# FMC_HPC_UFL_DEBUG_HPC_EF.net
KiCad netlist of a schematic drawn in Altium Designer
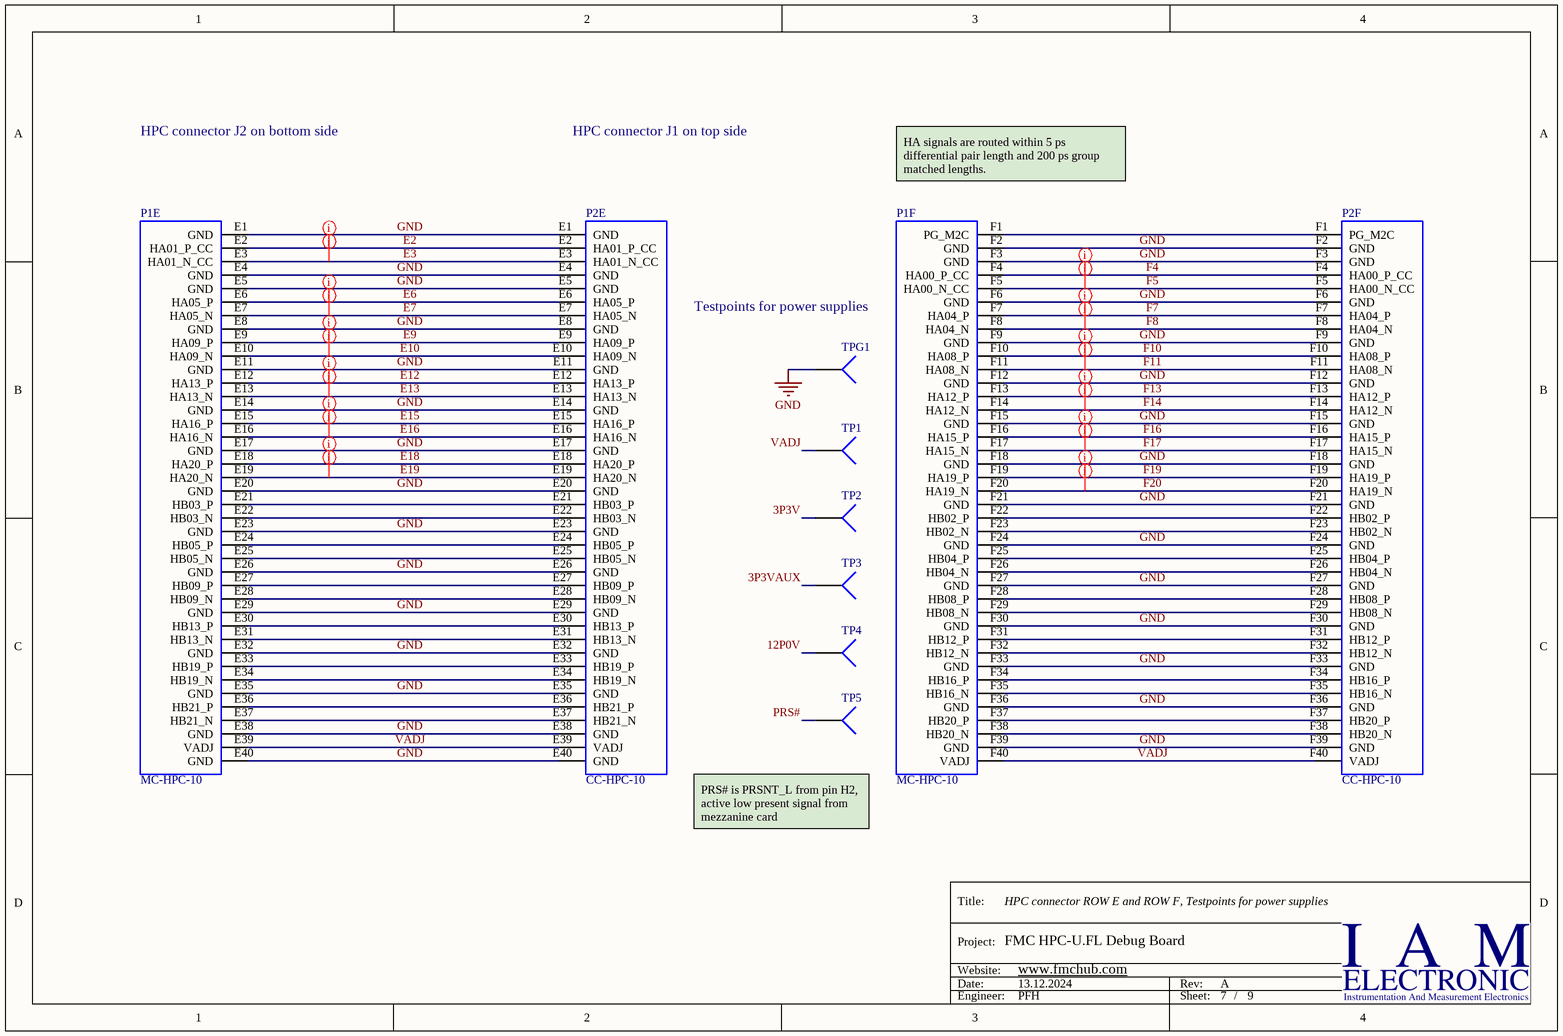
[diagram p0: FMC_HPC_UFL_DEBUG_HPC_EF.SchDoc]

(export (version "E")
  (design (tool "Eeschema 10.0.6"))
  (components
    (comp (ref "P1")
      (value "MC-HPC-10")
      (footprint "ASP-134488-01")
      (description "MC-HPC-10, FMC High-pin count connector, lead free, 400 I/Os, male, 10 mm mated stack height")
      (fields (field (name "MANUFACTURER") "Samtec") (field (name "PART") "ASP-134488-01"))
      (libsource (lib "VITA_57_FMC") (part "MC-HPC-10"))
    )
    (comp (ref "P2")
      (value "CC-HPC-10")
      (footprint "ASP-134486-01")
      (description "CC-HPC-10, FMC High-pin count connector, lead free, 400 I/Os, female, 10 mm mated stack height")
      (fields (field (name "MANUFACTURER") "Samtec") (field (name "PART") "ASP-134486-01"))
      (libsource (lib "VITA_57_FMC") (part "CC-HPC-10"))
    )
    (comp (ref "TP1")
      (value "~")
      (footprint "PIN1")
      (description "Socket")
      (fields (field (name "PUBLISHER") "Altium Limited"))
      (libsource (lib "Miscellaneous Connectors") (part "Socket"))
    )
    (comp (ref "TP2")
      (value "~")
      (footprint "PIN1")
      (description "Socket")
      (fields (field (name "PUBLISHER") "Altium Limited"))
      (libsource (lib "Miscellaneous Connectors") (part "Socket"))
    )
    (comp (ref "TP3")
      (value "~")
      (footprint "PIN1")
      (description "Socket")
      (fields (field (name "PUBLISHER") "Altium Limited"))
      (libsource (lib "Miscellaneous Connectors") (part "Socket"))
    )
    (comp (ref "TP4")
      (value "~")
      (footprint "PIN1")
      (description "Socket")
      (fields (field (name "PUBLISHER") "Altium Limited"))
      (libsource (lib "Miscellaneous Connectors") (part "Socket"))
    )
    (comp (ref "TP5")
      (value "~")
      (footprint "PIN1")
      (description "Socket")
      (fields (field (name "PUBLISHER") "Altium Limited"))
      (libsource (lib "Miscellaneous Connectors") (part "Socket"))
    )
    (comp (ref "TPG1")
      (value "~")
      (footprint "PIN1")
      (description "Socket")
      (fields (field (name "PUBLISHER") "Altium Limited"))
      (libsource (lib "Miscellaneous Connectors") (part "Socket"))
    )
  )
  (nets
    (net (code "1") (name "/3P3V") (class "Default")
      (node (ref "TP2") (pin "1") (pinfunction "1_1") (pintype "passive"))
    )
    (net (code "2") (name "/3P3VAUX") (class "Default")
      (node (ref "TP3") (pin "1") (pinfunction "1_1") (pintype "passive"))
    )
    (net (code "3") (name "/12P0V") (class "Default")
      (node (ref "TP4") (pin "1") (pinfunction "1_1") (pintype "passive"))
    )
    (net (code "4") (name "/E2") (class "Default")
      (node (ref "P1") (pin "E2") (pinfunction "HA01_P_CC_E2") (pintype "passive"))
      (node (ref "P2") (pin "E2") (pinfunction "HA01_P_CC_E2") (pintype "passive"))
    )
    (net (code "5") (name "/E3") (class "Default")
      (node (ref "P1") (pin "E3") (pinfunction "HA01_N_CC_E3") (pintype "passive"))
      (node (ref "P2") (pin "E3") (pinfunction "HA01_N_CC_E3") (pintype "passive"))
    )
    (net (code "6") (name "/E6") (class "Default")
      (node (ref "P1") (pin "E6") (pinfunction "HA05_P_E6") (pintype "passive"))
      (node (ref "P2") (pin "E6") (pinfunction "HA05_P_E6") (pintype "passive"))
    )
    (net (code "7") (name "/E7") (class "Default")
      (node (ref "P1") (pin "E7") (pinfunction "HA05_N_E7") (pintype "passive"))
      (node (ref "P2") (pin "E7") (pinfunction "HA05_N_E7") (pintype "passive"))
    )
    (net (code "8") (name "/E9") (class "Default")
      (node (ref "P1") (pin "E9") (pinfunction "HA09_P_E9") (pintype "passive"))
      (node (ref "P2") (pin "E9") (pinfunction "HA09_P_E9") (pintype "passive"))
    )
    (net (code "9") (name "/E10") (class "Default")
      (node (ref "P1") (pin "E10") (pinfunction "HA09_N_E10") (pintype "passive"))
      (node (ref "P2") (pin "E10") (pinfunction "HA09_N_E10") (pintype "passive"))
    )
    (net (code "10") (name "/E12") (class "Default")
      (node (ref "P1") (pin "E12") (pinfunction "HA13_P_E12") (pintype "passive"))
      (node (ref "P2") (pin "E12") (pinfunction "HA13_P_E12") (pintype "passive"))
    )
    (net (code "11") (name "/E13") (class "Default")
      (node (ref "P1") (pin "E13") (pinfunction "HA13_N_E13") (pintype "passive"))
      (node (ref "P2") (pin "E13") (pinfunction "HA13_N_E13") (pintype "passive"))
    )
    (net (code "12") (name "/E15") (class "Default")
      (node (ref "P1") (pin "E15") (pinfunction "HA16_P_E15") (pintype "passive"))
      (node (ref "P2") (pin "E15") (pinfunction "HA16_P_E15") (pintype "passive"))
    )
    (net (code "13") (name "/E16") (class "Default")
      (node (ref "P1") (pin "E16") (pinfunction "HA16_N_E16") (pintype "passive"))
      (node (ref "P2") (pin "E16") (pinfunction "HA16_N_E16") (pintype "passive"))
    )
    (net (code "14") (name "/E18") (class "Default")
      (node (ref "P1") (pin "E18") (pinfunction "HA20_P_E18") (pintype "passive"))
      (node (ref "P2") (pin "E18") (pinfunction "HA20_P_E18") (pintype "passive"))
    )
    (net (code "15") (name "/E19") (class "Default")
      (node (ref "P1") (pin "E19") (pinfunction "HA20_N_E19") (pintype "passive"))
      (node (ref "P2") (pin "E19") (pinfunction "HA20_N_E19") (pintype "passive"))
    )
    (net (code "16") (name "/F4") (class "Default")
      (node (ref "P1") (pin "F4") (pinfunction "HA00_P_CC_F4") (pintype "passive"))
      (node (ref "P2") (pin "F4") (pinfunction "HA00_P_CC_F4") (pintype "passive"))
    )
    (net (code "17") (name "/F5") (class "Default")
      (node (ref "P1") (pin "F5") (pinfunction "HA00_N_CC_F5") (pintype "passive"))
      (node (ref "P2") (pin "F5") (pinfunction "HA00_N_CC_F5") (pintype "passive"))
    )
    (net (code "18") (name "/F7") (class "Default")
      (node (ref "P1") (pin "F7") (pinfunction "HA04_P_F7") (pintype "passive"))
      (node (ref "P2") (pin "F7") (pinfunction "HA04_P_F7") (pintype "passive"))
    )
    (net (code "19") (name "/F8") (class "Default")
      (node (ref "P1") (pin "F8") (pinfunction "HA04_N_F8") (pintype "passive"))
      (node (ref "P2") (pin "F8") (pinfunction "HA04_N_F8") (pintype "passive"))
    )
    (net (code "20") (name "/F10") (class "Default")
      (node (ref "P1") (pin "F10") (pinfunction "HA08_P_F10") (pintype "passive"))
      (node (ref "P2") (pin "F10") (pinfunction "HA08_P_F10") (pintype "passive"))
    )
    (net (code "21") (name "/F11") (class "Default")
      (node (ref "P1") (pin "F11") (pinfunction "HA08_N_F11") (pintype "passive"))
      (node (ref "P2") (pin "F11") (pinfunction "HA08_N_F11") (pintype "passive"))
    )
    (net (code "22") (name "/F13") (class "Default")
      (node (ref "P1") (pin "F13") (pinfunction "HA12_P_F13") (pintype "passive"))
      (node (ref "P2") (pin "F13") (pinfunction "HA12_P_F13") (pintype "passive"))
    )
    (net (code "23") (name "/F14") (class "Default")
      (node (ref "P1") (pin "F14") (pinfunction "HA12_N_F14") (pintype "passive"))
      (node (ref "P2") (pin "F14") (pinfunction "HA12_N_F14") (pintype "passive"))
    )
    (net (code "24") (name "/F16") (class "Default")
      (node (ref "P1") (pin "F16") (pinfunction "HA15_P_F16") (pintype "passive"))
      (node (ref "P2") (pin "F16") (pinfunction "HA15_P_F16") (pintype "passive"))
    )
    (net (code "25") (name "/F17") (class "Default")
      (node (ref "P1") (pin "F17") (pinfunction "HA15_N_F17") (pintype "passive"))
      (node (ref "P2") (pin "F17") (pinfunction "HA15_N_F17") (pintype "passive"))
    )
    (net (code "26") (name "/F19") (class "Default")
      (node (ref "P1") (pin "F19") (pinfunction "HA19_P_F19") (pintype "passive"))
      (node (ref "P2") (pin "F19") (pinfunction "HA19_P_F19") (pintype "passive"))
    )
    (net (code "27") (name "/F20") (class "Default")
      (node (ref "P1") (pin "F20") (pinfunction "HA19_N_F20") (pintype "passive"))
      (node (ref "P2") (pin "F20") (pinfunction "HA19_N_F20") (pintype "passive"))
    )
    (net (code "28") (name "/PRS#") (class "Default")
      (node (ref "TP5") (pin "1") (pinfunction "1_1") (pintype "passive"))
    )
    (net (code "29") (name "/VADJ") (class "Default")
      (node (ref "P1") (pin "E39") (pinfunction "VADJ_E39") (pintype "passive"))
      (node (ref "P1") (pin "F40") (pinfunction "VADJ_F40") (pintype "passive"))
      (node (ref "P2") (pin "E39") (pinfunction "VADJ_E39") (pintype "passive"))
      (node (ref "P2") (pin "F40") (pinfunction "VADJ_F40") (pintype "passive"))
      (node (ref "TP1") (pin "1") (pinfunction "1_1") (pintype "passive"))
    )
    (net (code "30") (name "GND") (class "Default")
      (node (ref "P1") (pin "E1") (pinfunction "GND_E1") (pintype "passive"))
      (node (ref "P1") (pin "E11") (pinfunction "GND_E11") (pintype "passive"))
      (node (ref "P1") (pin "E14") (pinfunction "GND_E14") (pintype "passive"))
      (node (ref "P1") (pin "E17") (pinfunction "GND_E17") (pintype "passive"))
      (node (ref "P1") (pin "E20") (pinfunction "GND_E20") (pintype "passive"))
      (node (ref "P1") (pin "E23") (pinfunction "GND_E23") (pintype "passive"))
      (node (ref "P1") (pin "E26") (pinfunction "GND_E26") (pintype "passive"))
      (node (ref "P1") (pin "E29") (pinfunction "GND_E29") (pintype "passive"))
      (node (ref "P1") (pin "E32") (pinfunction "GND_E32") (pintype "passive"))
      (node (ref "P1") (pin "E35") (pinfunction "GND_E35") (pintype "passive"))
      (node (ref "P1") (pin "E38") (pinfunction "GND_E38") (pintype "passive"))
      (node (ref "P1") (pin "E4") (pinfunction "GND_E4") (pintype "passive"))
      (node (ref "P1") (pin "E40") (pinfunction "GND_E40") (pintype "passive"))
      (node (ref "P1") (pin "E5") (pinfunction "GND_E5") (pintype "passive"))
      (node (ref "P1") (pin "E8") (pinfunction "GND_E8") (pintype "passive"))
      (node (ref "P1") (pin "F12") (pinfunction "GND_F12") (pintype "passive"))
      (node (ref "P1") (pin "F15") (pinfunction "GND_F15") (pintype "passive"))
      (node (ref "P1") (pin "F18") (pinfunction "GND_F18") (pintype "passive"))
      (node (ref "P1") (pin "F2") (pinfunction "GND_F2") (pintype "passive"))
      (node (ref "P1") (pin "F21") (pinfunction "GND_F21") (pintype "passive"))
      (node (ref "P1") (pin "F24") (pinfunction "GND_F24") (pintype "passive"))
      (node (ref "P1") (pin "F27") (pinfunction "GND_F27") (pintype "passive"))
      (node (ref "P1") (pin "F3") (pinfunction "GND_F3") (pintype "passive"))
      (node (ref "P1") (pin "F30") (pinfunction "GND_F30") (pintype "passive"))
      (node (ref "P1") (pin "F33") (pinfunction "GND_F33") (pintype "passive"))
      (node (ref "P1") (pin "F36") (pinfunction "GND_F36") (pintype "passive"))
      (node (ref "P1") (pin "F39") (pinfunction "GND_F39") (pintype "passive"))
      (node (ref "P1") (pin "F6") (pinfunction "GND_F6") (pintype "passive"))
      (node (ref "P1") (pin "F9") (pinfunction "GND_F9") (pintype "passive"))
      (node (ref "P2") (pin "E1") (pinfunction "GND_E1") (pintype "passive"))
      (node (ref "P2") (pin "E11") (pinfunction "GND_E11") (pintype "passive"))
      (node (ref "P2") (pin "E14") (pinfunction "GND_E14") (pintype "passive"))
      (node (ref "P2") (pin "E17") (pinfunction "GND_E17") (pintype "passive"))
      (node (ref "P2") (pin "E20") (pinfunction "GND_E20") (pintype "passive"))
      (node (ref "P2") (pin "E23") (pinfunction "GND_E23") (pintype "passive"))
      (node (ref "P2") (pin "E26") (pinfunction "GND_E26") (pintype "passive"))
      (node (ref "P2") (pin "E29") (pinfunction "GND_E29") (pintype "passive"))
      (node (ref "P2") (pin "E32") (pinfunction "GND_E32") (pintype "passive"))
      (node (ref "P2") (pin "E35") (pinfunction "GND_E35") (pintype "passive"))
      (node (ref "P2") (pin "E38") (pinfunction "GND_E38") (pintype "passive"))
      (node (ref "P2") (pin "E4") (pinfunction "GND_E4") (pintype "passive"))
      (node (ref "P2") (pin "E40") (pinfunction "GND_E40") (pintype "passive"))
      (node (ref "P2") (pin "E5") (pinfunction "GND_E5") (pintype "passive"))
      (node (ref "P2") (pin "E8") (pinfunction "GND_E8") (pintype "passive"))
      (node (ref "P2") (pin "F12") (pinfunction "GND_F12") (pintype "passive"))
      (node (ref "P2") (pin "F15") (pinfunction "GND_F15") (pintype "passive"))
      (node (ref "P2") (pin "F18") (pinfunction "GND_F18") (pintype "passive"))
      (node (ref "P2") (pin "F2") (pinfunction "GND_F2") (pintype "passive"))
      (node (ref "P2") (pin "F21") (pinfunction "GND_F21") (pintype "passive"))
      (node (ref "P2") (pin "F24") (pinfunction "GND_F24") (pintype "passive"))
      (node (ref "P2") (pin "F27") (pinfunction "GND_F27") (pintype "passive"))
      (node (ref "P2") (pin "F3") (pinfunction "GND_F3") (pintype "passive"))
      (node (ref "P2") (pin "F30") (pinfunction "GND_F30") (pintype "passive"))
      (node (ref "P2") (pin "F33") (pinfunction "GND_F33") (pintype "passive"))
      (node (ref "P2") (pin "F36") (pinfunction "GND_F36") (pintype "passive"))
      (node (ref "P2") (pin "F39") (pinfunction "GND_F39") (pintype "passive"))
      (node (ref "P2") (pin "F6") (pinfunction "GND_F6") (pintype "passive"))
      (node (ref "P2") (pin "F9") (pinfunction "GND_F9") (pintype "passive"))
      (node (ref "TPG1") (pin "1") (pinfunction "1_1") (pintype "passive"))
    )
    (net (code "31") (name "Net-(P1E-HB03_N)") (class "Default")
      (node (ref "P1") (pin "E22") (pinfunction "HB03_N_E22") (pintype "passive"))
      (node (ref "P2") (pin "E22") (pinfunction "HB03_N_E22") (pintype "passive"))
    )
    (net (code "32") (name "Net-(P1E-HB03_P)") (class "Default")
      (node (ref "P1") (pin "E21") (pinfunction "HB03_P_E21") (pintype "passive"))
      (node (ref "P2") (pin "E21") (pinfunction "HB03_P_E21") (pintype "passive"))
    )
    (net (code "33") (name "Net-(P1E-HB05_N)") (class "Default")
      (node (ref "P1") (pin "E25") (pinfunction "HB05_N_E25") (pintype "passive"))
      (node (ref "P2") (pin "E25") (pinfunction "HB05_N_E25") (pintype "passive"))
    )
    (net (code "34") (name "Net-(P1E-HB05_P)") (class "Default")
      (node (ref "P1") (pin "E24") (pinfunction "HB05_P_E24") (pintype "passive"))
      (node (ref "P2") (pin "E24") (pinfunction "HB05_P_E24") (pintype "passive"))
    )
    (net (code "35") (name "Net-(P1E-HB09_N)") (class "Default")
      (node (ref "P1") (pin "E28") (pinfunction "HB09_N_E28") (pintype "passive"))
      (node (ref "P2") (pin "E28") (pinfunction "HB09_N_E28") (pintype "passive"))
    )
    (net (code "36") (name "Net-(P1E-HB09_P)") (class "Default")
      (node (ref "P1") (pin "E27") (pinfunction "HB09_P_E27") (pintype "passive"))
      (node (ref "P2") (pin "E27") (pinfunction "HB09_P_E27") (pintype "passive"))
    )
    (net (code "37") (name "Net-(P1E-HB13_N)") (class "Default")
      (node (ref "P1") (pin "E31") (pinfunction "HB13_N_E31") (pintype "passive"))
      (node (ref "P2") (pin "E31") (pinfunction "HB13_N_E31") (pintype "passive"))
    )
    (net (code "38") (name "Net-(P1E-HB13_P)") (class "Default")
      (node (ref "P1") (pin "E30") (pinfunction "HB13_P_E30") (pintype "passive"))
      (node (ref "P2") (pin "E30") (pinfunction "HB13_P_E30") (pintype "passive"))
    )
    (net (code "39") (name "Net-(P1E-HB19_N)") (class "Default")
      (node (ref "P1") (pin "E34") (pinfunction "HB19_N_E34") (pintype "passive"))
      (node (ref "P2") (pin "E34") (pinfunction "HB19_N_E34") (pintype "passive"))
    )
    (net (code "40") (name "Net-(P1E-HB19_P)") (class "Default")
      (node (ref "P1") (pin "E33") (pinfunction "HB19_P_E33") (pintype "passive"))
      (node (ref "P2") (pin "E33") (pinfunction "HB19_P_E33") (pintype "passive"))
    )
    (net (code "41") (name "Net-(P1E-HB21_N)") (class "Default")
      (node (ref "P1") (pin "E37") (pinfunction "HB21_N_E37") (pintype "passive"))
      (node (ref "P2") (pin "E37") (pinfunction "HB21_N_E37") (pintype "passive"))
    )
    (net (code "42") (name "Net-(P1E-HB21_P)") (class "Default")
      (node (ref "P1") (pin "E36") (pinfunction "HB21_P_E36") (pintype "passive"))
      (node (ref "P2") (pin "E36") (pinfunction "HB21_P_E36") (pintype "passive"))
    )
    (net (code "43") (name "Net-(P1F-HB02_N)") (class "Default")
      (node (ref "P1") (pin "F23") (pinfunction "HB02_N_F23") (pintype "passive"))
      (node (ref "P2") (pin "F23") (pinfunction "HB02_N_F23") (pintype "passive"))
    )
    (net (code "44") (name "Net-(P1F-HB02_P)") (class "Default")
      (node (ref "P1") (pin "F22") (pinfunction "HB02_P_F22") (pintype "passive"))
      (node (ref "P2") (pin "F22") (pinfunction "HB02_P_F22") (pintype "passive"))
    )
    (net (code "45") (name "Net-(P1F-HB04_N)") (class "Default")
      (node (ref "P1") (pin "F26") (pinfunction "HB04_N_F26") (pintype "passive"))
      (node (ref "P2") (pin "F26") (pinfunction "HB04_N_F26") (pintype "passive"))
    )
    (net (code "46") (name "Net-(P1F-HB04_P)") (class "Default")
      (node (ref "P1") (pin "F25") (pinfunction "HB04_P_F25") (pintype "passive"))
      (node (ref "P2") (pin "F25") (pinfunction "HB04_P_F25") (pintype "passive"))
    )
    (net (code "47") (name "Net-(P1F-HB08_N)") (class "Default")
      (node (ref "P1") (pin "F29") (pinfunction "HB08_N_F29") (pintype "passive"))
      (node (ref "P2") (pin "F29") (pinfunction "HB08_N_F29") (pintype "passive"))
    )
    (net (code "48") (name "Net-(P1F-HB08_P)") (class "Default")
      (node (ref "P1") (pin "F28") (pinfunction "HB08_P_F28") (pintype "passive"))
      (node (ref "P2") (pin "F28") (pinfunction "HB08_P_F28") (pintype "passive"))
    )
    (net (code "49") (name "Net-(P1F-HB12_N)") (class "Default")
      (node (ref "P1") (pin "F32") (pinfunction "HB12_N_F32") (pintype "passive"))
      (node (ref "P2") (pin "F32") (pinfunction "HB12_N_F32") (pintype "passive"))
    )
    (net (code "50") (name "Net-(P1F-HB12_P)") (class "Default")
      (node (ref "P1") (pin "F31") (pinfunction "HB12_P_F31") (pintype "passive"))
      (node (ref "P2") (pin "F31") (pinfunction "HB12_P_F31") (pintype "passive"))
    )
    (net (code "51") (name "Net-(P1F-HB16_N)") (class "Default")
      (node (ref "P1") (pin "F35") (pinfunction "HB16_N_F35") (pintype "passive"))
      (node (ref "P2") (pin "F35") (pinfunction "HB16_N_F35") (pintype "passive"))
    )
    (net (code "52") (name "Net-(P1F-HB16_P)") (class "Default")
      (node (ref "P1") (pin "F34") (pinfunction "HB16_P_F34") (pintype "passive"))
      (node (ref "P2") (pin "F34") (pinfunction "HB16_P_F34") (pintype "passive"))
    )
    (net (code "53") (name "Net-(P1F-HB20_N)") (class "Default")
      (node (ref "P1") (pin "F38") (pinfunction "HB20_N_F38") (pintype "passive"))
      (node (ref "P2") (pin "F38") (pinfunction "HB20_N_F38") (pintype "passive"))
    )
    (net (code "54") (name "Net-(P1F-HB20_P)") (class "Default")
      (node (ref "P1") (pin "F37") (pinfunction "HB20_P_F37") (pintype "passive"))
      (node (ref "P2") (pin "F37") (pinfunction "HB20_P_F37") (pintype "passive"))
    )
    (net (code "55") (name "Net-(P1F-PG_M2C)") (class "Default")
      (node (ref "P1") (pin "F1") (pinfunction "PG_M2C_F1") (pintype "passive"))
      (node (ref "P2") (pin "F1") (pinfunction "PG_M2C_F1") (pintype "passive"))
    )
  )
)
